# CR.net
KiCad netlist of a schematic drawn in Altium Designer
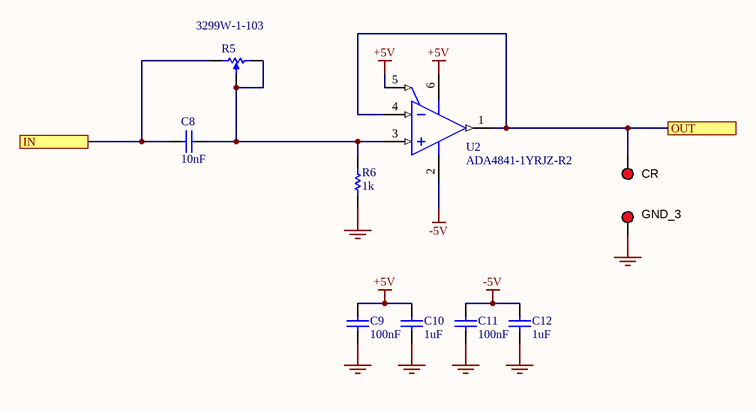
[diagram p0: CR.SchDoc]

(export (version "E")
  (design (tool "Eeschema 10.0.6"))
  (components
    (comp (ref "C8")
      (value "10nF")
      (footprint "CAPC0603(1608)100_N")
      (description "10nF Film")
      (fields (field (name "TOLERANCE") "Â±20%"))
      (libsource (lib "Altium Content Vault") (part "CAP"))
    )
    (comp (ref "C9")
      (value "100nF")
      (footprint "CAPC0603(1608)100_N")
      (description "CAP 100nF 25V ±20% 0603 (1608 Metric) Thickness 1mm SMD")
      (fields (field (name "TOLERANCE") "Â±20%"))
      (libsource (lib "Altium Content Vault") (part "CAP"))
    )
    (comp (ref "C10")
      (value "1uF")
      (footprint "CAPC0603(1608)100_N")
      (description "CAP 1uF 25V ±20% 0603 (1608 Metric) Thickness 1mm SMD")
      (fields (field (name "TOLERANCE") "Â±20%"))
      (libsource (lib "Altium Content Vault") (part "CAP"))
    )
    (comp (ref "C11")
      (value "100nF")
      (footprint "CAPC0603(1608)100_N")
      (description "CAP 100nF 25V ±20% 0603 (1608 Metric) Thickness 1mm SMD")
      (fields (field (name "TOLERANCE") "Â±20%"))
      (libsource (lib "Altium Content Vault") (part "CAP"))
    )
    (comp (ref "C12")
      (value "1uF")
      (footprint "CAPC0603(1608)100_N")
      (description "CAP 1uF 25V ±20% 0603 (1608 Metric) Thickness 1mm SMD")
      (fields (field (name "TOLERANCE") "Â±20%"))
      (libsource (lib "Altium Content Vault") (part "CAP"))
    )
    (comp (ref "CR")
      (value "5010")
      (footprint "KSTN-5010_V")
      (description "Test Point, Red, Through Hole, RoHS, Bulk")
      (libsource (lib "Altium Content Vault") (part "TESTPOINT_RED"))
    )
    (comp (ref "GND_3")
      (value "5010")
      (footprint "KSTN-5010_V")
      (description "Test Point, Red, Through Hole, RoHS, Bulk")
      (libsource (lib "Altium Content Vault") (part "TESTPOINT_RED"))
    )
    (comp (ref "R5")
      (value "3299W-1-103")
      (footprint "BOUR-3299W-3_V")
      (fields (field (name "MANUFACTURER") "Bourns") (field (name "TOLERANCE") "10%"))
      (libsource (lib "Altium Content Vault") (part "RES-ADJ-3_A"))
    )
    (comp (ref "R6")
      (value "1k")
      (footprint "RESC0603(1608)_N")
      (description "1k 1% Metal film")
      (fields (field (name "TOLERANCE") "1 %") (field (name "POWER") "0.1 W"))
      (libsource (lib "Altium Content Vault") (part "RES"))
    )
    (comp (ref "U2")
      (value "ADA4841-1YRJZ-R2")
      (footprint "ADI-RJ-6_M")
      (fields (field (name "MANUFACTURER") "Analog Devices") (field (name "GENERIC PART NUMBER") "ADA4841-1"))
      (libsource (lib "Altium Content Vault") (part "ADI-ADA48X1-1-RJ-6"))
    )
  )
  (nets
    (net (code "1") (name "+5V") (class "Default")
      (node (ref "C10") (pin "2") (pinfunction "2_2") (pintype "passive"))
      (node (ref "C9") (pin "2") (pinfunction "2_2") (pintype "passive"))
      (node (ref "U2") (pin "5") (pinfunction "~{POWER_DOWN}_5") (pintype "input"))
      (node (ref "U2") (pin "6") (pinfunction "+VS_6") (pintype "power_in"))
    )
    (net (code "2") (name "-5V") (class "Default")
      (node (ref "C11") (pin "2") (pinfunction "2_2") (pintype "passive"))
      (node (ref "C12") (pin "2") (pinfunction "2_2") (pintype "passive"))
      (node (ref "U2") (pin "2") (pinfunction "-VS_2") (pintype "power_in"))
    )
    (net (code "3") (name "/IN") (class "Default")
      (node (ref "C8") (pin "2") (pinfunction "2_2") (pintype "passive"))
      (node (ref "R5") (pin "1") (pinfunction "1_1") (pintype "passive"))
    )
    (net (code "4") (name "/OUT") (class "Default")
      (node (ref "CR") (pin "1") (pinfunction "1_1") (pintype "passive"))
      (node (ref "U2") (pin "1") (pinfunction "VOUT_1") (pintype "output"))
      (node (ref "U2") (pin "4") (pinfunction "-IN_4") (pintype "input"))
    )
    (net (code "5") (name "GND") (class "Default")
      (node (ref "C10") (pin "1") (pinfunction "1_1") (pintype "passive"))
      (node (ref "C11") (pin "1") (pinfunction "1_1") (pintype "passive"))
      (node (ref "C12") (pin "1") (pinfunction "1_1") (pintype "passive"))
      (node (ref "C9") (pin "1") (pinfunction "1_1") (pintype "passive"))
      (node (ref "GND_3") (pin "1") (pinfunction "1_1") (pintype "passive"))
      (node (ref "R6") (pin "1") (pinfunction "1_1") (pintype "passive"))
    )
    (net (code "6") (name "Net-(U2-+IN)") (class "Default")
      (node (ref "C8") (pin "1") (pinfunction "1_1") (pintype "passive"))
      (node (ref "R5") (pin "2") (pinfunction "2_2") (pintype "passive"))
      (node (ref "R5") (pin "3") (pinfunction "3_3") (pintype "passive"))
      (node (ref "R6") (pin "2") (pinfunction "2_2") (pintype "passive"))
      (node (ref "U2") (pin "3") (pinfunction "+IN_3") (pintype "input"))
    )
  )
)
